# IR_Sensors.net
KiCad netlist of a schematic drawn in Altium Designer
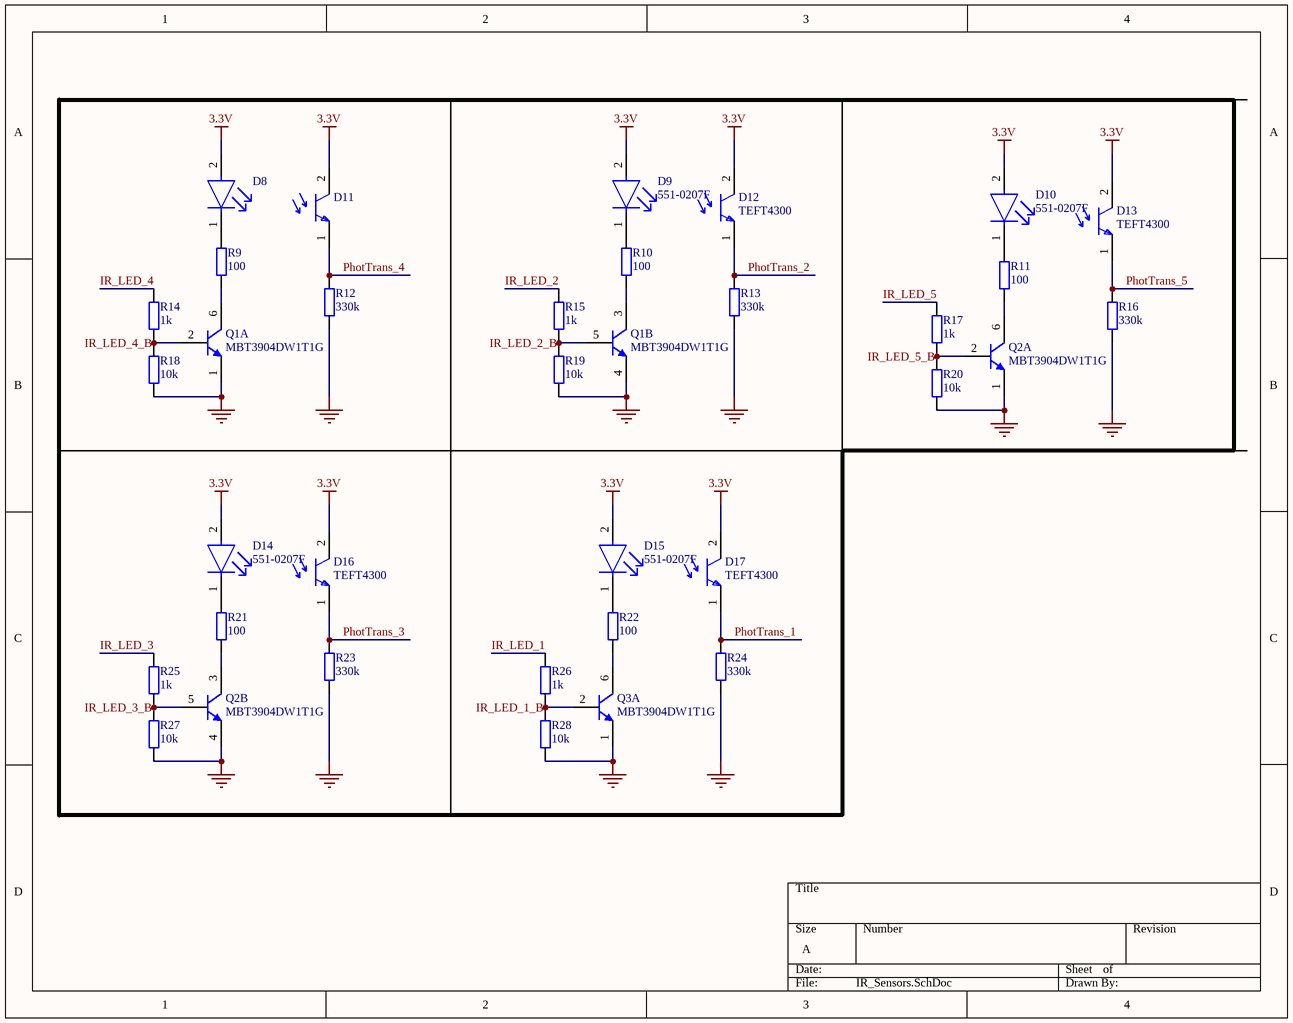
[diagram p0: IR_Sensors.SchDoc]

(export (version "E")
  (design (tool "Eeschema 10.0.6"))
  (components
    (comp (ref "D8")
      (value "551-0207F")
      (footprint "FP-551-0207F-MFG")
      (description "LED 3MM HIGH EFF GREEN")
      (libsource (lib "Altium Content Vault") (part "8706943c75ba83719d021d2fdc84c58"))
    )
    (comp (ref "D9")
      (value "551-0207F")
      (footprint "FP-551-0207F-MFG")
      (description "LED 3MM HIGH EFF GREEN")
      (libsource (lib "Altium Content Vault") (part "8706943c75ba83719d021d2fdc84c58"))
    )
    (comp (ref "D10")
      (value "551-0207F")
      (footprint "FP-551-0207F-MFG")
      (description "LED 3MM HIGH EFF GREEN")
      (libsource (lib "Altium Content Vault") (part "8706943c75ba83719d021d2fdc84c58"))
    )
    (comp (ref "D11")
      (value "TEFT4300")
      (footprint "FP-6_544-5269_01-4-MFG")
      (description "TEFT4300 PHOTOTRANSISTOR 3.0MM WIDE VIEW / Phototransistor IR Chip Silicon 925nm 2-Pin T-1")
      (libsource (lib "Altium Content Vault") (part "fcf5d96e013ede1c9e051256f92411f"))
    )
    (comp (ref "D12")
      (value "TEFT4300")
      (footprint "FP-6_544-5269_01-4-MFG")
      (description "TEFT4300 PHOTOTRANSISTOR 3.0MM WIDE VIEW / Phototransistor IR Chip Silicon 925nm 2-Pin T-1")
      (libsource (lib "Altium Content Vault") (part "fcf5d96e013ede1c9e051256f92411f"))
    )
    (comp (ref "D13")
      (value "TEFT4300")
      (footprint "FP-6_544-5269_01-4-MFG")
      (description "TEFT4300 PHOTOTRANSISTOR 3.0MM WIDE VIEW / Phototransistor IR Chip Silicon 925nm 2-Pin T-1")
      (libsource (lib "Altium Content Vault") (part "fcf5d96e013ede1c9e051256f92411f"))
    )
    (comp (ref "D14")
      (value "551-0207F")
      (footprint "FP-551-0207F-MFG")
      (description "LED 3MM HIGH EFF GREEN")
      (libsource (lib "Altium Content Vault") (part "8706943c75ba83719d021d2fdc84c58"))
    )
    (comp (ref "D15")
      (value "551-0207F")
      (footprint "FP-551-0207F-MFG")
      (description "LED 3MM HIGH EFF GREEN")
      (libsource (lib "Altium Content Vault") (part "8706943c75ba83719d021d2fdc84c58"))
    )
    (comp (ref "D16")
      (value "TEFT4300")
      (footprint "FP-6_544-5269_01-4-MFG")
      (description "TEFT4300 PHOTOTRANSISTOR 3.0MM WIDE VIEW / Phototransistor IR Chip Silicon 925nm 2-Pin T-1")
      (libsource (lib "Altium Content Vault") (part "fcf5d96e013ede1c9e051256f92411f"))
    )
    (comp (ref "D17")
      (value "TEFT4300")
      (footprint "FP-6_544-5269_01-4-MFG")
      (description "TEFT4300 PHOTOTRANSISTOR 3.0MM WIDE VIEW / Phototransistor IR Chip Silicon 925nm 2-Pin T-1")
      (libsource (lib "Altium Content Vault") (part "fcf5d96e013ede1c9e051256f92411f"))
    )
    (comp (ref "Q1")
      (value "MBT3904DW1T1G")
      (footprint "ONSC-SOT-363-6-419B-02_W_V")
      (description "Dual General Purpose Transistors, 6-Pin SOT-363, Pb-Free, Tape and Reel")
      (fields (field (name "MANUFACTURER") "On Semiconductor"))
      (libsource (lib "Altium Content Vault") (part "ONSC-NPN_NPN-6_F"))
    )
    (comp (ref "Q2")
      (value "MBT3904DW1T1G")
      (footprint "ONSC-SOT-363-6-419B-02_W_V")
      (description "Dual General Purpose Transistors, 6-Pin SOT-363, Pb-Free, Tape and Reel")
      (fields (field (name "MANUFACTURER") "On Semiconductor"))
      (libsource (lib "Altium Content Vault") (part "ONSC-NPN_NPN-6_F"))
    )
    (comp (ref "Q3")
      (value "MBT3904DW1T1G")
      (footprint "ONSC-SOT-363-6-419B-02_W_V")
      (description "Dual General Purpose Transistors, 6-Pin SOT-363, Pb-Free, Tape and Reel")
      (fields (field (name "MANUFACTURER") "On Semiconductor"))
      (libsource (lib "Altium Content Vault") (part "ONSC-NPN_NPN-6_F"))
    )
    (comp (ref "R9")
      (value "100")
      (footprint "RES_0603")
      (description "Resistor SMD 0603")
      (libsource (lib "Schematic-Lib-PhilsLab") (part "RES_0603"))
    )
    (comp (ref "R10")
      (value "100")
      (footprint "RES_0603")
      (description "Resistor SMD 0603")
      (libsource (lib "Schematic-Lib-PhilsLab") (part "RES_0603"))
    )
    (comp (ref "R11")
      (value "100")
      (footprint "RES_0603")
      (description "Resistor SMD 0603")
      (libsource (lib "Schematic-Lib-PhilsLab") (part "RES_0603"))
    )
    (comp (ref "R12")
      (value "330k")
      (footprint "RES_0603")
      (description "Resistor SMD 0603")
      (libsource (lib "Schematic-Lib-PhilsLab") (part "RES_0603"))
    )
    (comp (ref "R13")
      (value "330k")
      (footprint "RES_0603")
      (description "Resistor SMD 0603")
      (libsource (lib "Schematic-Lib-PhilsLab") (part "RES_0603"))
    )
    (comp (ref "R14")
      (value "1k")
      (footprint "RES_0603")
      (description "Resistor SMD 0603")
      (libsource (lib "Schematic-Lib-PhilsLab") (part "RES_0603"))
    )
    (comp (ref "R15")
      (value "1k")
      (footprint "RES_0603")
      (description "Resistor SMD 0603")
      (libsource (lib "Schematic-Lib-PhilsLab") (part "RES_0603"))
    )
    (comp (ref "R16")
      (value "330k")
      (footprint "RES_0603")
      (description "Resistor SMD 0603")
      (libsource (lib "Schematic-Lib-PhilsLab") (part "RES_0603"))
    )
    (comp (ref "R17")
      (value "1k")
      (footprint "RES_0603")
      (description "Resistor SMD 0603")
      (libsource (lib "Schematic-Lib-PhilsLab") (part "RES_0603"))
    )
    (comp (ref "R18")
      (value "10k")
      (footprint "RES_0603")
      (description "Resistor SMD 0603")
      (libsource (lib "Schematic-Lib-PhilsLab") (part "RES_0603"))
    )
    (comp (ref "R19")
      (value "10k")
      (footprint "RES_0603")
      (description "Resistor SMD 0603")
      (libsource (lib "Schematic-Lib-PhilsLab") (part "RES_0603"))
    )
    (comp (ref "R20")
      (value "10k")
      (footprint "RES_0603")
      (description "Resistor SMD 0603")
      (libsource (lib "Schematic-Lib-PhilsLab") (part "RES_0603"))
    )
    (comp (ref "R21")
      (value "100")
      (footprint "RES_0603")
      (description "Resistor SMD 0603")
      (libsource (lib "Schematic-Lib-PhilsLab") (part "RES_0603"))
    )
    (comp (ref "R22")
      (value "100")
      (footprint "RES_0603")
      (description "Resistor SMD 0603")
      (libsource (lib "Schematic-Lib-PhilsLab") (part "RES_0603"))
    )
    (comp (ref "R23")
      (value "330k")
      (footprint "RES_0603")
      (description "Resistor SMD 0603")
      (libsource (lib "Schematic-Lib-PhilsLab") (part "RES_0603"))
    )
    (comp (ref "R24")
      (value "330k")
      (footprint "RES_0603")
      (description "Resistor SMD 0603")
      (libsource (lib "Schematic-Lib-PhilsLab") (part "RES_0603"))
    )
    (comp (ref "R25")
      (value "1k")
      (footprint "RES_0603")
      (description "Resistor SMD 0603")
      (libsource (lib "Schematic-Lib-PhilsLab") (part "RES_0603"))
    )
    (comp (ref "R26")
      (value "1k")
      (footprint "RES_0603")
      (description "Resistor SMD 0603")
      (libsource (lib "Schematic-Lib-PhilsLab") (part "RES_0603"))
    )
    (comp (ref "R27")
      (value "10k")
      (footprint "RES_0603")
      (description "Resistor SMD 0603")
      (libsource (lib "Schematic-Lib-PhilsLab") (part "RES_0603"))
    )
    (comp (ref "R28")
      (value "10k")
      (footprint "RES_0603")
      (description "Resistor SMD 0603")
      (libsource (lib "Schematic-Lib-PhilsLab") (part "RES_0603"))
    )
  )
  (nets
    (net (code "1") (name "/IR_LED_1") (class "Default")
      (node (ref "R26") (pin "2") (pinfunction "2_2") (pintype "passive"))
    )
    (net (code "2") (name "/IR_LED_1_B") (class "Default")
      (node (ref "Q3") (pin "2") (pinfunction "B_2") (pintype "passive"))
      (node (ref "R26") (pin "1") (pinfunction "1_1") (pintype "passive"))
      (node (ref "R28") (pin "2") (pinfunction "2_2") (pintype "passive"))
    )
    (net (code "3") (name "/IR_LED_2") (class "Default")
      (node (ref "R15") (pin "2") (pinfunction "2_2") (pintype "passive"))
    )
    (net (code "4") (name "/IR_LED_2_B") (class "Default")
      (node (ref "Q1") (pin "5") (pinfunction "B_5") (pintype "passive"))
      (node (ref "R15") (pin "1") (pinfunction "1_1") (pintype "passive"))
      (node (ref "R19") (pin "2") (pinfunction "2_2") (pintype "passive"))
    )
    (net (code "5") (name "/IR_LED_3") (class "Default")
      (node (ref "R25") (pin "2") (pinfunction "2_2") (pintype "passive"))
    )
    (net (code "6") (name "/IR_LED_3_B") (class "Default")
      (node (ref "Q2") (pin "5") (pinfunction "B_5") (pintype "passive"))
      (node (ref "R25") (pin "1") (pinfunction "1_1") (pintype "passive"))
      (node (ref "R27") (pin "2") (pinfunction "2_2") (pintype "passive"))
    )
    (net (code "7") (name "/IR_LED_4") (class "Default")
      (node (ref "R14") (pin "2") (pinfunction "2_2") (pintype "passive"))
    )
    (net (code "8") (name "/IR_LED_4_B") (class "Default")
      (node (ref "Q1") (pin "2") (pinfunction "B_2") (pintype "passive"))
      (node (ref "R14") (pin "1") (pinfunction "1_1") (pintype "passive"))
      (node (ref "R18") (pin "2") (pinfunction "2_2") (pintype "passive"))
    )
    (net (code "9") (name "/IR_LED_5") (class "Default")
      (node (ref "R17") (pin "2") (pinfunction "2_2") (pintype "passive"))
    )
    (net (code "10") (name "/IR_LED_5_B") (class "Default")
      (node (ref "Q2") (pin "2") (pinfunction "B_2") (pintype "passive"))
      (node (ref "R17") (pin "1") (pinfunction "1_1") (pintype "passive"))
      (node (ref "R20") (pin "2") (pinfunction "2_2") (pintype "passive"))
    )
    (net (code "11") (name "/PhotTrans_1") (class "Default")
      (node (ref "D17") (pin "1") (pinfunction "E_1") (pintype "passive"))
      (node (ref "R24") (pin "2") (pinfunction "2_2") (pintype "passive"))
    )
    (net (code "12") (name "/PhotTrans_2") (class "Default")
      (node (ref "D12") (pin "1") (pinfunction "E_1") (pintype "passive"))
      (node (ref "R13") (pin "2") (pinfunction "2_2") (pintype "passive"))
    )
    (net (code "13") (name "/PhotTrans_3") (class "Default")
      (node (ref "D16") (pin "1") (pinfunction "E_1") (pintype "passive"))
      (node (ref "R23") (pin "2") (pinfunction "2_2") (pintype "passive"))
    )
    (net (code "14") (name "/PhotTrans_4") (class "Default")
      (node (ref "D11") (pin "1") (pinfunction "E_1") (pintype "passive"))
      (node (ref "R12") (pin "2") (pinfunction "2_2") (pintype "passive"))
    )
    (net (code "15") (name "/PhotTrans_5") (class "Default")
      (node (ref "D13") (pin "1") (pinfunction "E_1") (pintype "passive"))
      (node (ref "R16") (pin "2") (pinfunction "2_2") (pintype "passive"))
    )
    (net (code "16") (name "3.3V") (class "Default")
      (node (ref "D10") (pin "2") (pinfunction "A_2") (pintype "passive"))
      (node (ref "D11") (pin "2") (pinfunction "C_2") (pintype "passive"))
      (node (ref "D12") (pin "2") (pinfunction "C_2") (pintype "passive"))
      (node (ref "D13") (pin "2") (pinfunction "C_2") (pintype "passive"))
      (node (ref "D14") (pin "2") (pinfunction "A_2") (pintype "passive"))
      (node (ref "D15") (pin "2") (pinfunction "A_2") (pintype "passive"))
      (node (ref "D16") (pin "2") (pinfunction "C_2") (pintype "passive"))
      (node (ref "D17") (pin "2") (pinfunction "C_2") (pintype "passive"))
      (node (ref "D8") (pin "2") (pinfunction "A_2") (pintype "passive"))
      (node (ref "D9") (pin "2") (pinfunction "A_2") (pintype "passive"))
    )
    (net (code "17") (name "GND") (class "Default")
      (node (ref "Q1") (pin "1") (pinfunction "E_1") (pintype "passive"))
      (node (ref "Q1") (pin "4") (pinfunction "E_4") (pintype "passive"))
      (node (ref "Q2") (pin "1") (pinfunction "E_1") (pintype "passive"))
      (node (ref "Q2") (pin "4") (pinfunction "E_4") (pintype "passive"))
      (node (ref "Q3") (pin "1") (pinfunction "E_1") (pintype "passive"))
      (node (ref "R12") (pin "1") (pinfunction "1_1") (pintype "passive"))
      (node (ref "R13") (pin "1") (pinfunction "1_1") (pintype "passive"))
      (node (ref "R16") (pin "1") (pinfunction "1_1") (pintype "passive"))
      (node (ref "R18") (pin "1") (pinfunction "1_1") (pintype "passive"))
      (node (ref "R19") (pin "1") (pinfunction "1_1") (pintype "passive"))
      (node (ref "R20") (pin "1") (pinfunction "1_1") (pintype "passive"))
      (node (ref "R23") (pin "1") (pinfunction "1_1") (pintype "passive"))
      (node (ref "R24") (pin "1") (pinfunction "1_1") (pintype "passive"))
      (node (ref "R27") (pin "1") (pinfunction "1_1") (pintype "passive"))
      (node (ref "R28") (pin "1") (pinfunction "1_1") (pintype "passive"))
    )
    (net (code "18") (name "Net-(D8-C)") (class "Default")
      (node (ref "D8") (pin "1") (pinfunction "C_1") (pintype "passive"))
      (node (ref "R9") (pin "2") (pinfunction "2_2") (pintype "passive"))
    )
    (net (code "19") (name "Net-(D9-C)") (class "Default")
      (node (ref "D9") (pin "1") (pinfunction "C_1") (pintype "passive"))
      (node (ref "R10") (pin "2") (pinfunction "2_2") (pintype "passive"))
    )
    (net (code "20") (name "Net-(D10-C)") (class "Default")
      (node (ref "D10") (pin "1") (pinfunction "C_1") (pintype "passive"))
      (node (ref "R11") (pin "2") (pinfunction "2_2") (pintype "passive"))
    )
    (net (code "21") (name "Net-(D14-C)") (class "Default")
      (node (ref "D14") (pin "1") (pinfunction "C_1") (pintype "passive"))
      (node (ref "R21") (pin "2") (pinfunction "2_2") (pintype "passive"))
    )
    (net (code "22") (name "Net-(D15-C)") (class "Default")
      (node (ref "D15") (pin "1") (pinfunction "C_1") (pintype "passive"))
      (node (ref "R22") (pin "2") (pinfunction "2_2") (pintype "passive"))
    )
    (net (code "23") (name "Net-(Q1A-C)") (class "Default")
      (node (ref "Q1") (pin "6") (pinfunction "C_6") (pintype "passive"))
      (node (ref "R9") (pin "1") (pinfunction "1_1") (pintype "passive"))
    )
    (net (code "24") (name "Net-(Q1B-C)") (class "Default")
      (node (ref "Q1") (pin "3") (pinfunction "C_3") (pintype "passive"))
      (node (ref "R10") (pin "1") (pinfunction "1_1") (pintype "passive"))
    )
    (net (code "25") (name "Net-(Q2A-C)") (class "Default")
      (node (ref "Q2") (pin "6") (pinfunction "C_6") (pintype "passive"))
      (node (ref "R11") (pin "1") (pinfunction "1_1") (pintype "passive"))
    )
    (net (code "26") (name "Net-(Q2B-C)") (class "Default")
      (node (ref "Q2") (pin "3") (pinfunction "C_3") (pintype "passive"))
      (node (ref "R21") (pin "1") (pinfunction "1_1") (pintype "passive"))
    )
    (net (code "27") (name "Net-(Q3A-C)") (class "Default")
      (node (ref "Q3") (pin "6") (pinfunction "C_6") (pintype "passive"))
      (node (ref "R22") (pin "1") (pinfunction "1_1") (pintype "passive"))
    )
  )
)
